# Servo_Header.net
KiCad netlist of a schematic drawn in EAGLE
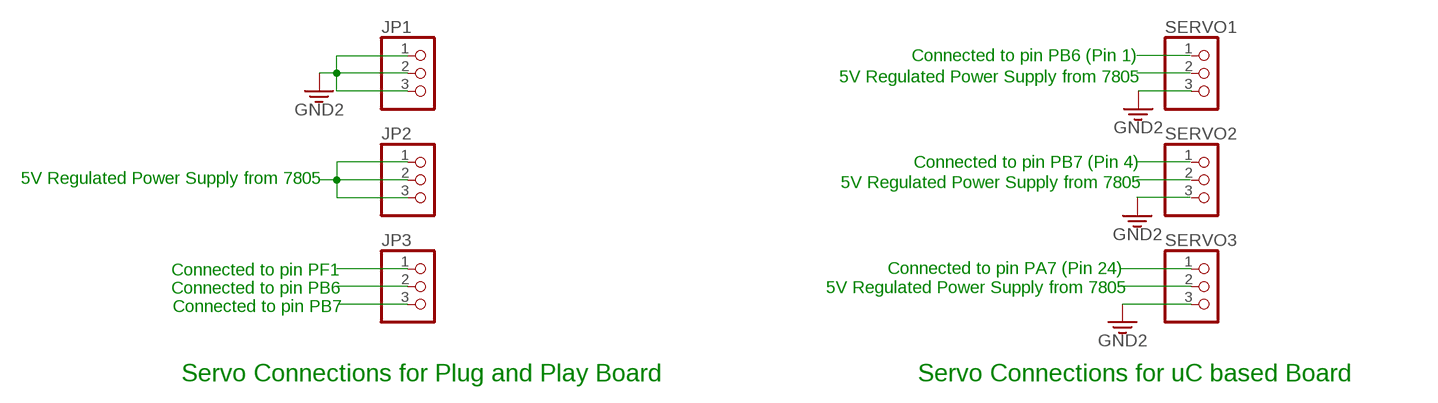
[diagram p0: schematic, sheet 1]

(export (version "E")
  (design (tool "Eeschema 10.0.6"))
  (components
    (comp (ref "JP1")
      (value "PINHD-1X3")
      (footprint "eagle-import:1X03")
      (libsource (lib "eagle-import") (part "PINHD-1X3"))
    )
    (comp (ref "JP2")
      (value "PINHD-1X3")
      (footprint "eagle-import:1X03")
      (libsource (lib "eagle-import") (part "PINHD-1X3"))
    )
    (comp (ref "JP3")
      (value "PINHD-1X3")
      (footprint "eagle-import:1X03")
      (libsource (lib "eagle-import") (part "PINHD-1X3"))
    )
    (comp (ref "SERVO1")
      (value "PINHD-1X3")
      (footprint "eagle-import:1X03")
      (libsource (lib "eagle-import") (part "PINHD-1X3"))
    )
    (comp (ref "SERVO2")
      (value "PINHD-1X3")
      (footprint "eagle-import:1X03")
      (libsource (lib "eagle-import") (part "PINHD-1X3"))
    )
    (comp (ref "SERVO3")
      (value "PINHD-1X3")
      (footprint "eagle-import:1X03")
      (libsource (lib "eagle-import") (part "PINHD-1X3"))
    )
  )
  (nets
    (net (code "1") (name "GND2") (class "Default")
      (node (ref "JP1") (pin "1") (pinfunction "1_1") (pintype "passive"))
      (node (ref "JP1") (pin "2") (pinfunction "2_2") (pintype "passive"))
      (node (ref "JP1") (pin "3") (pinfunction "3_3") (pintype "passive"))
    )
    (net (code "2") (name "Net-(JP2-Pad1)") (class "Default")
      (node (ref "JP2") (pin "1") (pinfunction "1_1") (pintype "passive"))
      (node (ref "JP2") (pin "2") (pinfunction "2_2") (pintype "passive"))
      (node (ref "JP2") (pin "3") (pinfunction "3_3") (pintype "passive"))
    )
    (net (code "3") (name "unconnected-(JP3-Pad1)") (class "Default")
      (node (ref "JP3") (pin "1") (pinfunction "1_1") (pintype "passive"))
    )
    (net (code "4") (name "unconnected-(JP3-Pad2)") (class "Default")
      (node (ref "JP3") (pin "2") (pinfunction "2_2") (pintype "passive"))
    )
    (net (code "5") (name "unconnected-(JP3-Pad3)") (class "Default")
      (node (ref "JP3") (pin "3") (pinfunction "3_3") (pintype "passive"))
    )
    (net (code "6") (name "unconnected-(SERVO1-Pad1)") (class "Default")
      (node (ref "SERVO1") (pin "1") (pinfunction "1_1") (pintype "passive"))
    )
    (net (code "7") (name "unconnected-(SERVO1-Pad2)") (class "Default")
      (node (ref "SERVO1") (pin "2") (pinfunction "2_2") (pintype "passive"))
    )
    (net (code "8") (name "unconnected-(SERVO1-Pad3)") (class "Default")
      (node (ref "SERVO1") (pin "3") (pinfunction "3_3") (pintype "passive"))
    )
    (net (code "9") (name "unconnected-(SERVO2-Pad1)") (class "Default")
      (node (ref "SERVO2") (pin "1") (pinfunction "1_1") (pintype "passive"))
    )
    (net (code "10") (name "unconnected-(SERVO2-Pad2)") (class "Default")
      (node (ref "SERVO2") (pin "2") (pinfunction "2_2") (pintype "passive"))
    )
    (net (code "11") (name "unconnected-(SERVO2-Pad3)") (class "Default")
      (node (ref "SERVO2") (pin "3") (pinfunction "3_3") (pintype "passive"))
    )
    (net (code "12") (name "unconnected-(SERVO3-Pad1)") (class "Default")
      (node (ref "SERVO3") (pin "1") (pinfunction "1_1") (pintype "passive"))
    )
    (net (code "13") (name "unconnected-(SERVO3-Pad2)") (class "Default")
      (node (ref "SERVO3") (pin "2") (pinfunction "2_2") (pintype "passive"))
    )
    (net (code "14") (name "unconnected-(SERVO3-Pad3)") (class "Default")
      (node (ref "SERVO3") (pin "3") (pinfunction "3_3") (pintype "passive"))
    )
  )
)
